# KeyJam_Header.net
KiCad netlist of a schematic drawn in EAGLE
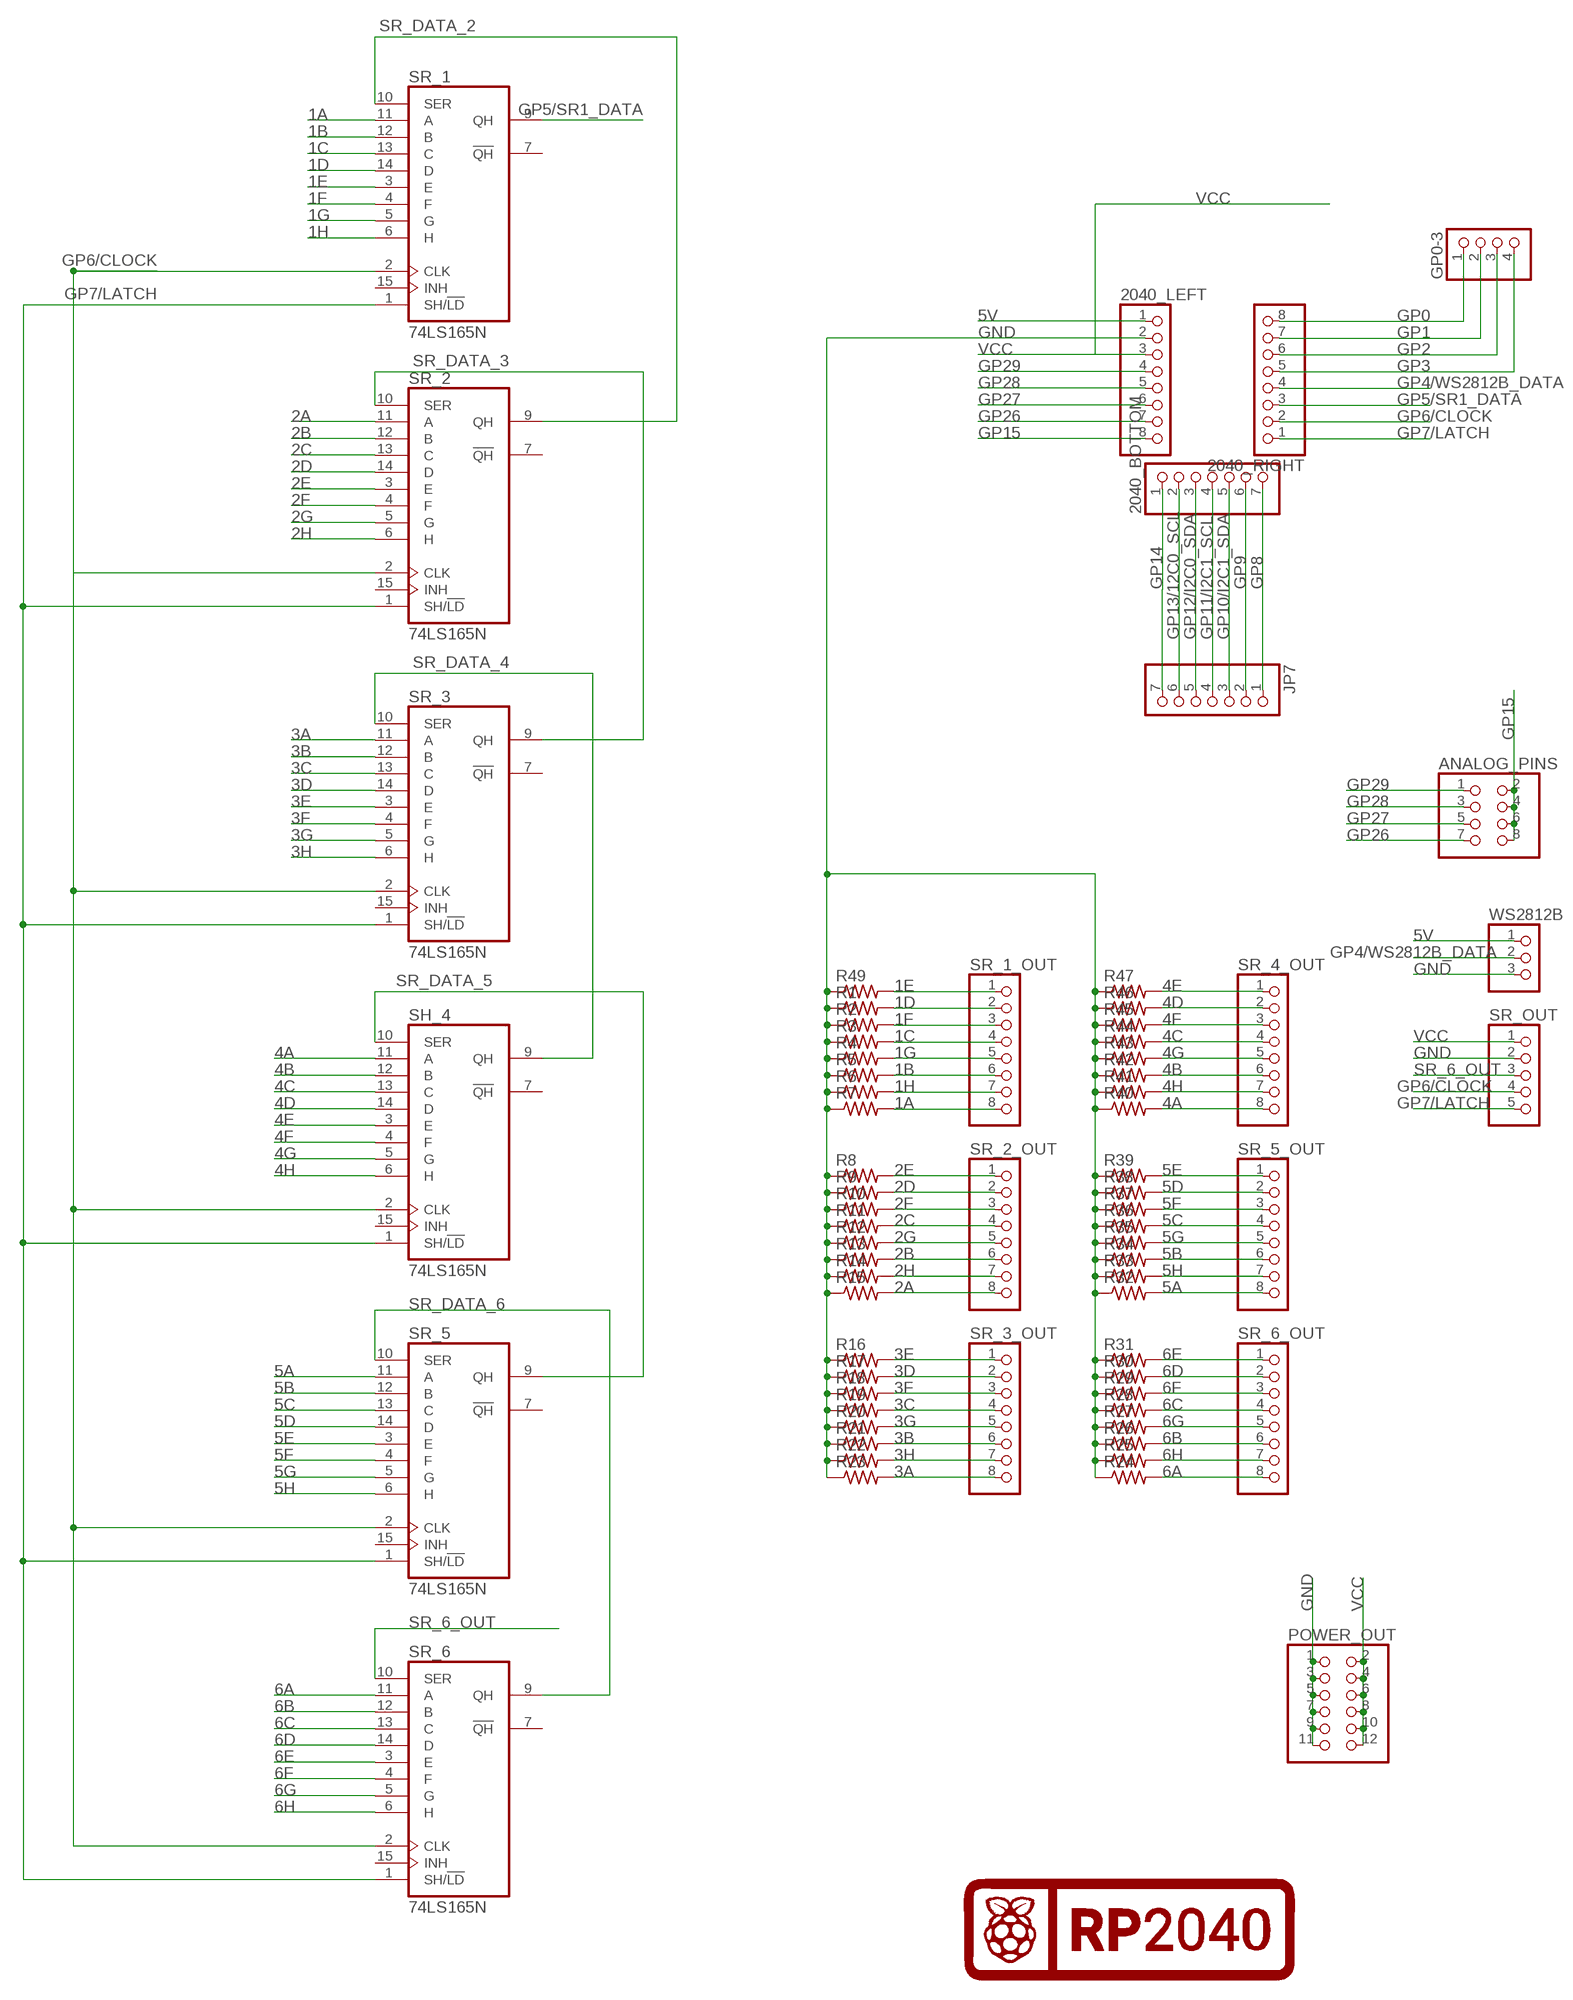
[diagram p0: schematic, sheet 1]

(export (version "E")
  (design (tool "Eeschema 10.0.6"))
  (components
    (comp (ref "2040_BOTTOM")
      (value "PINHD-1X7")
      (footprint "eagle-import:1X07")
      (libsource (lib "eagle-import") (part "PINHD-1X7"))
    )
    (comp (ref "2040_LEFT")
      (value "PINHD-1X8")
      (footprint "eagle-import:1X08")
      (libsource (lib "eagle-import") (part "PINHD-1X8"))
    )
    (comp (ref "2040_RIGHT")
      (value "PINHD-1X8")
      (footprint "eagle-import:1X08")
      (libsource (lib "eagle-import") (part "PINHD-1X8"))
    )
    (comp (ref "ANALOG_PINS")
      (value "PINHD-2X4")
      (footprint "eagle-import:2X04")
      (libsource (lib "eagle-import") (part "PINHD-2X4"))
    )
    (comp (ref "GP0-3")
      (value "PINHD-1X4")
      (footprint "eagle-import:1X04")
      (libsource (lib "eagle-import") (part "PINHD-1X4"))
    )
    (comp (ref "JP7")
      (value "PINHD-1X7")
      (footprint "eagle-import:1X07")
      (libsource (lib "eagle-import") (part "PINHD-1X7"))
    )
    (comp (ref "POWER_OUT")
      (value "PINHD-2X6")
      (footprint "eagle-import:2X06")
      (libsource (lib "eagle-import") (part "PINHD-2X6"))
    )
    (comp (ref "R1")
      (value "R-US_R1206")
      (footprint "eagle-import:R1206")
      (libsource (lib "eagle-import") (part "R-US_R1206"))
    )
    (comp (ref "R2")
      (value "R-US_R1206")
      (footprint "eagle-import:R1206")
      (libsource (lib "eagle-import") (part "R-US_R1206"))
    )
    (comp (ref "R3")
      (value "R-US_R1206")
      (footprint "eagle-import:R1206")
      (libsource (lib "eagle-import") (part "R-US_R1206"))
    )
    (comp (ref "R4")
      (value "R-US_R1206")
      (footprint "eagle-import:R1206")
      (libsource (lib "eagle-import") (part "R-US_R1206"))
    )
    (comp (ref "R5")
      (value "R-US_R1206")
      (footprint "eagle-import:R1206")
      (libsource (lib "eagle-import") (part "R-US_R1206"))
    )
    (comp (ref "R6")
      (value "R-US_R1206")
      (footprint "eagle-import:R1206")
      (libsource (lib "eagle-import") (part "R-US_R1206"))
    )
    (comp (ref "R7")
      (value "R-US_R1206")
      (footprint "eagle-import:R1206")
      (libsource (lib "eagle-import") (part "R-US_R1206"))
    )
    (comp (ref "R8")
      (value "R-US_R1206")
      (footprint "eagle-import:R1206")
      (libsource (lib "eagle-import") (part "R-US_R1206"))
    )
    (comp (ref "R9")
      (value "R-US_R1206")
      (footprint "eagle-import:R1206")
      (libsource (lib "eagle-import") (part "R-US_R1206"))
    )
    (comp (ref "R10")
      (value "R-US_R1206")
      (footprint "eagle-import:R1206")
      (libsource (lib "eagle-import") (part "R-US_R1206"))
    )
    (comp (ref "R11")
      (value "R-US_R1206")
      (footprint "eagle-import:R1206")
      (libsource (lib "eagle-import") (part "R-US_R1206"))
    )
    (comp (ref "R12")
      (value "R-US_R1206")
      (footprint "eagle-import:R1206")
      (libsource (lib "eagle-import") (part "R-US_R1206"))
    )
    (comp (ref "R13")
      (value "R-US_R1206")
      (footprint "eagle-import:R1206")
      (libsource (lib "eagle-import") (part "R-US_R1206"))
    )
    (comp (ref "R14")
      (value "R-US_R1206")
      (footprint "eagle-import:R1206")
      (libsource (lib "eagle-import") (part "R-US_R1206"))
    )
    (comp (ref "R15")
      (value "R-US_R1206")
      (footprint "eagle-import:R1206")
      (libsource (lib "eagle-import") (part "R-US_R1206"))
    )
    (comp (ref "R16")
      (value "R-US_R1206")
      (footprint "eagle-import:R1206")
      (libsource (lib "eagle-import") (part "R-US_R1206"))
    )
    (comp (ref "R17")
      (value "R-US_R1206")
      (footprint "eagle-import:R1206")
      (libsource (lib "eagle-import") (part "R-US_R1206"))
    )
    (comp (ref "R18")
      (value "R-US_R1206")
      (footprint "eagle-import:R1206")
      (libsource (lib "eagle-import") (part "R-US_R1206"))
    )
    (comp (ref "R19")
      (value "R-US_R1206")
      (footprint "eagle-import:R1206")
      (libsource (lib "eagle-import") (part "R-US_R1206"))
    )
    (comp (ref "R20")
      (value "R-US_R1206")
      (footprint "eagle-import:R1206")
      (libsource (lib "eagle-import") (part "R-US_R1206"))
    )
    (comp (ref "R21")
      (value "R-US_R1206")
      (footprint "eagle-import:R1206")
      (libsource (lib "eagle-import") (part "R-US_R1206"))
    )
    (comp (ref "R22")
      (value "R-US_R1206")
      (footprint "eagle-import:R1206")
      (libsource (lib "eagle-import") (part "R-US_R1206"))
    )
    (comp (ref "R23")
      (value "R-US_R1206")
      (footprint "eagle-import:R1206")
      (libsource (lib "eagle-import") (part "R-US_R1206"))
    )
    (comp (ref "R24")
      (value "R-US_R1206")
      (footprint "eagle-import:R1206")
      (libsource (lib "eagle-import") (part "R-US_R1206"))
    )
    (comp (ref "R25")
      (value "R-US_R1206")
      (footprint "eagle-import:R1206")
      (libsource (lib "eagle-import") (part "R-US_R1206"))
    )
    (comp (ref "R26")
      (value "R-US_R1206")
      (footprint "eagle-import:R1206")
      (libsource (lib "eagle-import") (part "R-US_R1206"))
    )
    (comp (ref "R27")
      (value "R-US_R1206")
      (footprint "eagle-import:R1206")
      (libsource (lib "eagle-import") (part "R-US_R1206"))
    )
    (comp (ref "R28")
      (value "R-US_R1206")
      (footprint "eagle-import:R1206")
      (libsource (lib "eagle-import") (part "R-US_R1206"))
    )
    (comp (ref "R29")
      (value "R-US_R1206")
      (footprint "eagle-import:R1206")
      (libsource (lib "eagle-import") (part "R-US_R1206"))
    )
    (comp (ref "R30")
      (value "R-US_R1206")
      (footprint "eagle-import:R1206")
      (libsource (lib "eagle-import") (part "R-US_R1206"))
    )
    (comp (ref "R31")
      (value "R-US_R1206")
      (footprint "eagle-import:R1206")
      (libsource (lib "eagle-import") (part "R-US_R1206"))
    )
    (comp (ref "R32")
      (value "R-US_R1206")
      (footprint "eagle-import:R1206")
      (libsource (lib "eagle-import") (part "R-US_R1206"))
    )
    (comp (ref "R33")
      (value "R-US_R1206")
      (footprint "eagle-import:R1206")
      (libsource (lib "eagle-import") (part "R-US_R1206"))
    )
    (comp (ref "R34")
      (value "R-US_R1206")
      (footprint "eagle-import:R1206")
      (libsource (lib "eagle-import") (part "R-US_R1206"))
    )
    (comp (ref "R35")
      (value "R-US_R1206")
      (footprint "eagle-import:R1206")
      (libsource (lib "eagle-import") (part "R-US_R1206"))
    )
    (comp (ref "R36")
      (value "R-US_R1206")
      (footprint "eagle-import:R1206")
      (libsource (lib "eagle-import") (part "R-US_R1206"))
    )
    (comp (ref "R37")
      (value "R-US_R1206")
      (footprint "eagle-import:R1206")
      (libsource (lib "eagle-import") (part "R-US_R1206"))
    )
    (comp (ref "R38")
      (value "R-US_R1206")
      (footprint "eagle-import:R1206")
      (libsource (lib "eagle-import") (part "R-US_R1206"))
    )
    (comp (ref "R39")
      (value "R-US_R1206")
      (footprint "eagle-import:R1206")
      (libsource (lib "eagle-import") (part "R-US_R1206"))
    )
    (comp (ref "R40")
      (value "R-US_R1206")
      (footprint "eagle-import:R1206")
      (libsource (lib "eagle-import") (part "R-US_R1206"))
    )
    (comp (ref "R41")
      (value "R-US_R1206")
      (footprint "eagle-import:R1206")
      (libsource (lib "eagle-import") (part "R-US_R1206"))
    )
    (comp (ref "R42")
      (value "R-US_R1206")
      (footprint "eagle-import:R1206")
      (libsource (lib "eagle-import") (part "R-US_R1206"))
    )
    (comp (ref "R43")
      (value "R-US_R1206")
      (footprint "eagle-import:R1206")
      (libsource (lib "eagle-import") (part "R-US_R1206"))
    )
    (comp (ref "R44")
      (value "R-US_R1206")
      (footprint "eagle-import:R1206")
      (libsource (lib "eagle-import") (part "R-US_R1206"))
    )
    (comp (ref "R45")
      (value "R-US_R1206")
      (footprint "eagle-import:R1206")
      (libsource (lib "eagle-import") (part "R-US_R1206"))
    )
    (comp (ref "R46")
      (value "R-US_R1206")
      (footprint "eagle-import:R1206")
      (libsource (lib "eagle-import") (part "R-US_R1206"))
    )
    (comp (ref "R47")
      (value "R-US_R1206")
      (footprint "eagle-import:R1206")
      (libsource (lib "eagle-import") (part "R-US_R1206"))
    )
    (comp (ref "R49")
      (value "R-US_R1206")
      (footprint "eagle-import:R1206")
      (libsource (lib "eagle-import") (part "R-US_R1206"))
    )
    (comp (ref "SH_4")
      (value "74LS165N")
      (footprint "eagle-import:DIL16")
      (libsource (lib "eagle-import") (part "74165NLS"))
    )
    (comp (ref "SR_1")
      (value "74LS165N")
      (footprint "eagle-import:DIL16")
      (libsource (lib "eagle-import") (part "74165NLS"))
    )
    (comp (ref "SR_1_OUT")
      (value "PINHD-1X8")
      (footprint "eagle-import:1X08")
      (libsource (lib "eagle-import") (part "PINHD-1X8"))
    )
    (comp (ref "SR_2")
      (value "74LS165N")
      (footprint "eagle-import:DIL16")
      (libsource (lib "eagle-import") (part "74165NLS"))
    )
    (comp (ref "SR_2_OUT")
      (value "PINHD-1X8")
      (footprint "eagle-import:1X08")
      (libsource (lib "eagle-import") (part "PINHD-1X8"))
    )
    (comp (ref "SR_3")
      (value "74LS165N")
      (footprint "eagle-import:DIL16")
      (libsource (lib "eagle-import") (part "74165NLS"))
    )
    (comp (ref "SR_3_OUT")
      (value "PINHD-1X8")
      (footprint "eagle-import:1X08")
      (libsource (lib "eagle-import") (part "PINHD-1X8"))
    )
    (comp (ref "SR_4_OUT")
      (value "PINHD-1X8")
      (footprint "eagle-import:1X08")
      (libsource (lib "eagle-import") (part "PINHD-1X8"))
    )
    (comp (ref "SR_5")
      (value "74LS165N")
      (footprint "eagle-import:DIL16")
      (libsource (lib "eagle-import") (part "74165NLS"))
    )
    (comp (ref "SR_5_OUT")
      (value "PINHD-1X8")
      (footprint "eagle-import:1X08")
      (libsource (lib "eagle-import") (part "PINHD-1X8"))
    )
    (comp (ref "SR_6")
      (value "74LS165N")
      (footprint "eagle-import:DIL16")
      (libsource (lib "eagle-import") (part "74165NLS"))
    )
    (comp (ref "SR_6_OUT")
      (value "PINHD-1X8")
      (footprint "eagle-import:1X08")
      (libsource (lib "eagle-import") (part "PINHD-1X8"))
    )
    (comp (ref "SR_OUT")
      (value "PINHD-1X5")
      (footprint "eagle-import:1X05")
      (libsource (lib "eagle-import") (part "PINHD-1X5"))
    )
    (comp (ref "U$1")
      (value "RASPI_RP2040_LOGO_20MM")
      (footprint "eagle-import:RASPI_RP2040_LOGO_20MM")
      (libsource (lib "eagle-import") (part "RASPI_RP2040_LOGO_20MM"))
    )
    (comp (ref "WS2812B")
      (value "PINHD-1X3")
      (footprint "eagle-import:1X03")
      (libsource (lib "eagle-import") (part "PINHD-1X3"))
    )
  )
  (nets
    (net (code "1") (name "/1A") (class "Default")
      (node (ref "R7") (pin "2") (pinfunction "2_2") (pintype "passive"))
      (node (ref "SR_1") (pin "11") (pinfunction "A_11") (pintype "input"))
      (node (ref "SR_1_OUT") (pin "8") (pinfunction "8_8") (pintype "passive"))
    )
    (net (code "2") (name "/1B") (class "Default")
      (node (ref "R5") (pin "2") (pinfunction "2_2") (pintype "passive"))
      (node (ref "SR_1") (pin "12") (pinfunction "B_12") (pintype "input"))
      (node (ref "SR_1_OUT") (pin "6") (pinfunction "6_6") (pintype "passive"))
    )
    (net (code "3") (name "/1C") (class "Default")
      (node (ref "R3") (pin "2") (pinfunction "2_2") (pintype "passive"))
      (node (ref "SR_1") (pin "13") (pinfunction "C_13") (pintype "input"))
      (node (ref "SR_1_OUT") (pin "4") (pinfunction "4_4") (pintype "passive"))
    )
    (net (code "4") (name "/1D") (class "Default")
      (node (ref "R1") (pin "2") (pinfunction "2_2") (pintype "passive"))
      (node (ref "SR_1") (pin "14") (pinfunction "D_14") (pintype "input"))
      (node (ref "SR_1_OUT") (pin "2") (pinfunction "2_2") (pintype "passive"))
    )
    (net (code "5") (name "/1E") (class "Default")
      (node (ref "R49") (pin "2") (pinfunction "2_2") (pintype "passive"))
      (node (ref "SR_1") (pin "3") (pinfunction "E_3") (pintype "input"))
      (node (ref "SR_1_OUT") (pin "1") (pinfunction "1_1") (pintype "passive"))
    )
    (net (code "6") (name "/1F") (class "Default")
      (node (ref "R2") (pin "2") (pinfunction "2_2") (pintype "passive"))
      (node (ref "SR_1") (pin "4") (pinfunction "F_4") (pintype "input"))
      (node (ref "SR_1_OUT") (pin "3") (pinfunction "3_3") (pintype "passive"))
    )
    (net (code "7") (name "/1G") (class "Default")
      (node (ref "R4") (pin "2") (pinfunction "2_2") (pintype "passive"))
      (node (ref "SR_1") (pin "5") (pinfunction "G_5") (pintype "input"))
      (node (ref "SR_1_OUT") (pin "5") (pinfunction "5_5") (pintype "passive"))
    )
    (net (code "8") (name "/1H") (class "Default")
      (node (ref "R6") (pin "2") (pinfunction "2_2") (pintype "passive"))
      (node (ref "SR_1") (pin "6") (pinfunction "H_6") (pintype "input"))
      (node (ref "SR_1_OUT") (pin "7") (pinfunction "7_7") (pintype "passive"))
    )
    (net (code "9") (name "/2A") (class "Default")
      (node (ref "R15") (pin "2") (pinfunction "2_2") (pintype "passive"))
      (node (ref "SR_2") (pin "11") (pinfunction "A_11") (pintype "input"))
      (node (ref "SR_2_OUT") (pin "8") (pinfunction "8_8") (pintype "passive"))
    )
    (net (code "10") (name "/2B") (class "Default")
      (node (ref "R13") (pin "2") (pinfunction "2_2") (pintype "passive"))
      (node (ref "SR_2") (pin "12") (pinfunction "B_12") (pintype "input"))
      (node (ref "SR_2_OUT") (pin "6") (pinfunction "6_6") (pintype "passive"))
    )
    (net (code "11") (name "/2C") (class "Default")
      (node (ref "R11") (pin "2") (pinfunction "2_2") (pintype "passive"))
      (node (ref "SR_2") (pin "13") (pinfunction "C_13") (pintype "input"))
      (node (ref "SR_2_OUT") (pin "4") (pinfunction "4_4") (pintype "passive"))
    )
    (net (code "12") (name "/2D") (class "Default")
      (node (ref "R9") (pin "2") (pinfunction "2_2") (pintype "passive"))
      (node (ref "SR_2") (pin "14") (pinfunction "D_14") (pintype "input"))
      (node (ref "SR_2_OUT") (pin "2") (pinfunction "2_2") (pintype "passive"))
    )
    (net (code "13") (name "/2E") (class "Default")
      (node (ref "R8") (pin "2") (pinfunction "2_2") (pintype "passive"))
      (node (ref "SR_2") (pin "3") (pinfunction "E_3") (pintype "input"))
      (node (ref "SR_2_OUT") (pin "1") (pinfunction "1_1") (pintype "passive"))
    )
    (net (code "14") (name "/2F") (class "Default")
      (node (ref "R10") (pin "2") (pinfunction "2_2") (pintype "passive"))
      (node (ref "SR_2") (pin "4") (pinfunction "F_4") (pintype "input"))
      (node (ref "SR_2_OUT") (pin "3") (pinfunction "3_3") (pintype "passive"))
    )
    (net (code "15") (name "/2G") (class "Default")
      (node (ref "R12") (pin "2") (pinfunction "2_2") (pintype "passive"))
      (node (ref "SR_2") (pin "5") (pinfunction "G_5") (pintype "input"))
      (node (ref "SR_2_OUT") (pin "5") (pinfunction "5_5") (pintype "passive"))
    )
    (net (code "16") (name "/2H") (class "Default")
      (node (ref "R14") (pin "2") (pinfunction "2_2") (pintype "passive"))
      (node (ref "SR_2") (pin "6") (pinfunction "H_6") (pintype "input"))
      (node (ref "SR_2_OUT") (pin "7") (pinfunction "7_7") (pintype "passive"))
    )
    (net (code "17") (name "/3A") (class "Default")
      (node (ref "R23") (pin "2") (pinfunction "2_2") (pintype "passive"))
      (node (ref "SR_3") (pin "11") (pinfunction "A_11") (pintype "input"))
      (node (ref "SR_3_OUT") (pin "8") (pinfunction "8_8") (pintype "passive"))
    )
    (net (code "18") (name "/3B") (class "Default")
      (node (ref "R21") (pin "2") (pinfunction "2_2") (pintype "passive"))
      (node (ref "SR_3") (pin "12") (pinfunction "B_12") (pintype "input"))
      (node (ref "SR_3_OUT") (pin "6") (pinfunction "6_6") (pintype "passive"))
    )
    (net (code "19") (name "/3C") (class "Default")
      (node (ref "R19") (pin "2") (pinfunction "2_2") (pintype "passive"))
      (node (ref "SR_3") (pin "13") (pinfunction "C_13") (pintype "input"))
      (node (ref "SR_3_OUT") (pin "4") (pinfunction "4_4") (pintype "passive"))
    )
    (net (code "20") (name "/3D") (class "Default")
      (node (ref "R17") (pin "2") (pinfunction "2_2") (pintype "passive"))
      (node (ref "SR_3") (pin "14") (pinfunction "D_14") (pintype "input"))
      (node (ref "SR_3_OUT") (pin "2") (pinfunction "2_2") (pintype "passive"))
    )
    (net (code "21") (name "/3E") (class "Default")
      (node (ref "R16") (pin "2") (pinfunction "2_2") (pintype "passive"))
      (node (ref "SR_3") (pin "3") (pinfunction "E_3") (pintype "input"))
      (node (ref "SR_3_OUT") (pin "1") (pinfunction "1_1") (pintype "passive"))
    )
    (net (code "22") (name "/3F") (class "Default")
      (node (ref "R18") (pin "2") (pinfunction "2_2") (pintype "passive"))
      (node (ref "SR_3") (pin "4") (pinfunction "F_4") (pintype "input"))
      (node (ref "SR_3_OUT") (pin "3") (pinfunction "3_3") (pintype "passive"))
    )
    (net (code "23") (name "/3G") (class "Default")
      (node (ref "R20") (pin "2") (pinfunction "2_2") (pintype "passive"))
      (node (ref "SR_3") (pin "5") (pinfunction "G_5") (pintype "input"))
      (node (ref "SR_3_OUT") (pin "5") (pinfunction "5_5") (pintype "passive"))
    )
    (net (code "24") (name "/3H") (class "Default")
      (node (ref "R22") (pin "2") (pinfunction "2_2") (pintype "passive"))
      (node (ref "SR_3") (pin "6") (pinfunction "H_6") (pintype "input"))
      (node (ref "SR_3_OUT") (pin "7") (pinfunction "7_7") (pintype "passive"))
    )
    (net (code "25") (name "/4A") (class "Default")
      (node (ref "R40") (pin "2") (pinfunction "2_2") (pintype "passive"))
      (node (ref "SH_4") (pin "11") (pinfunction "A_11") (pintype "input"))
      (node (ref "SR_4_OUT") (pin "8") (pinfunction "8_8") (pintype "passive"))
    )
    (net (code "26") (name "/4B") (class "Default")
      (node (ref "R42") (pin "2") (pinfunction "2_2") (pintype "passive"))
      (node (ref "SH_4") (pin "12") (pinfunction "B_12") (pintype "input"))
      (node (ref "SR_4_OUT") (pin "6") (pinfunction "6_6") (pintype "passive"))
    )
    (net (code "27") (name "/4C") (class "Default")
      (node (ref "R44") (pin "2") (pinfunction "2_2") (pintype "passive"))
      (node (ref "SH_4") (pin "13") (pinfunction "C_13") (pintype "input"))
      (node (ref "SR_4_OUT") (pin "4") (pinfunction "4_4") (pintype "passive"))
    )
    (net (code "28") (name "/4D") (class "Default")
      (node (ref "R46") (pin "2") (pinfunction "2_2") (pintype "passive"))
      (node (ref "SH_4") (pin "14") (pinfunction "D_14") (pintype "input"))
      (node (ref "SR_4_OUT") (pin "2") (pinfunction "2_2") (pintype "passive"))
    )
    (net (code "29") (name "/4E") (class "Default")
      (node (ref "R47") (pin "2") (pinfunction "2_2") (pintype "passive"))
      (node (ref "SH_4") (pin "3") (pinfunction "E_3") (pintype "input"))
      (node (ref "SR_4_OUT") (pin "1") (pinfunction "1_1") (pintype "passive"))
    )
    (net (code "30") (name "/4F") (class "Default")
      (node (ref "R45") (pin "2") (pinfunction "2_2") (pintype "passive"))
      (node (ref "SH_4") (pin "4") (pinfunction "F_4") (pintype "input"))
      (node (ref "SR_4_OUT") (pin "3") (pinfunction "3_3") (pintype "passive"))
    )
    (net (code "31") (name "/4G") (class "Default")
      (node (ref "R43") (pin "2") (pinfunction "2_2") (pintype "passive"))
      (node (ref "SH_4") (pin "5") (pinfunction "G_5") (pintype "input"))
      (node (ref "SR_4_OUT") (pin "5") (pinfunction "5_5") (pintype "passive"))
    )
    (net (code "32") (name "/4H") (class "Default")
      (node (ref "R41") (pin "2") (pinfunction "2_2") (pintype "passive"))
      (node (ref "SH_4") (pin "6") (pinfunction "H_6") (pintype "input"))
      (node (ref "SR_4_OUT") (pin "7") (pinfunction "7_7") (pintype "passive"))
    )
    (net (code "33") (name "/5A") (class "Default")
      (node (ref "R32") (pin "2") (pinfunction "2_2") (pintype "passive"))
      (node (ref "SR_5") (pin "11") (pinfunction "A_11") (pintype "input"))
      (node (ref "SR_5_OUT") (pin "8") (pinfunction "8_8") (pintype "passive"))
    )
    (net (code "34") (name "/5B") (class "Default")
      (node (ref "R34") (pin "2") (pinfunction "2_2") (pintype "passive"))
      (node (ref "SR_5") (pin "12") (pinfunction "B_12") (pintype "input"))
      (node (ref "SR_5_OUT") (pin "6") (pinfunction "6_6") (pintype "passive"))
    )
    (net (code "35") (name "/5C") (class "Default")
      (node (ref "R36") (pin "2") (pinfunction "2_2") (pintype "passive"))
      (node (ref "SR_5") (pin "13") (pinfunction "C_13") (pintype "input"))
      (node (ref "SR_5_OUT") (pin "4") (pinfunction "4_4") (pintype "passive"))
    )
    (net (code "36") (name "/5D") (class "Default")
      (node (ref "R38") (pin "2") (pinfunction "2_2") (pintype "passive"))
      (node (ref "SR_5") (pin "14") (pinfunction "D_14") (pintype "input"))
      (node (ref "SR_5_OUT") (pin "2") (pinfunction "2_2") (pintype "passive"))
    )
    (net (code "37") (name "/5E") (class "Default")
      (node (ref "R39") (pin "2") (pinfunction "2_2") (pintype "passive"))
      (node (ref "SR_5") (pin "3") (pinfunction "E_3") (pintype "input"))
      (node (ref "SR_5_OUT") (pin "1") (pinfunction "1_1") (pintype "passive"))
    )
    (net (code "38") (name "/5F") (class "Default")
      (node (ref "R37") (pin "2") (pinfunction "2_2") (pintype "passive"))
      (node (ref "SR_5") (pin "4") (pinfunction "F_4") (pintype "input"))
      (node (ref "SR_5_OUT") (pin "3") (pinfunction "3_3") (pintype "passive"))
    )
    (net (code "39") (name "/5G") (class "Default")
      (node (ref "R35") (pin "2") (pinfunction "2_2") (pintype "passive"))
      (node (ref "SR_5") (pin "5") (pinfunction "G_5") (pintype "input"))
      (node (ref "SR_5_OUT") (pin "5") (pinfunction "5_5") (pintype "passive"))
    )
    (net (code "40") (name "/5H") (class "Default")
      (node (ref "R33") (pin "2") (pinfunction "2_2") (pintype "passive"))
      (node (ref "SR_5") (pin "6") (pinfunction "H_6") (pintype "input"))
      (node (ref "SR_5_OUT") (pin "7") (pinfunction "7_7") (pintype "passive"))
    )
    (net (code "41") (name "/5V") (class "Default")
      (node (ref "2040_LEFT") (pin "1") (pinfunction "1_1") (pintype "passive"))
      (node (ref "WS2812B") (pin "1") (pinfunction "1_1") (pintype "passive"))
    )
    (net (code "42") (name "/6A") (class "Default")
      (node (ref "R24") (pin "2") (pinfunction "2_2") (pintype "passive"))
      (node (ref "SR_6") (pin "11") (pinfunction "A_11") (pintype "input"))
      (node (ref "SR_6_OUT") (pin "8") (pinfunction "8_8") (pintype "passive"))
    )
    (net (code "43") (name "/6B") (class "Default")
      (node (ref "R26") (pin "2") (pinfunction "2_2") (pintype "passive"))
      (node (ref "SR_6") (pin "12") (pinfunction "B_12") (pintype "input"))
      (node (ref "SR_6_OUT") (pin "6") (pinfunction "6_6") (pintype "passive"))
    )
    (net (code "44") (name "/6C") (class "Default")
      (node (ref "R28") (pin "2") (pinfunction "2_2") (pintype "passive"))
      (node (ref "SR_6") (pin "13") (pinfunction "C_13") (pintype "input"))
      (node (ref "SR_6_OUT") (pin "4") (pinfunction "4_4") (pintype "passive"))
    )
    (net (code "45") (name "/6D") (class "Default")
      (node (ref "R30") (pin "2") (pinfunction "2_2") (pintype "passive"))
      (node (ref "SR_6") (pin "14") (pinfunction "D_14") (pintype "input"))
      (node (ref "SR_6_OUT") (pin "2") (pinfunction "2_2") (pintype "passive"))
    )
    (net (code "46") (name "/6E") (class "Default")
      (node (ref "R31") (pin "2") (pinfunction "2_2") (pintype "passive"))
      (node (ref "SR_6") (pin "3") (pinfunction "E_3") (pintype "input"))
      (node (ref "SR_6_OUT") (pin "1") (pinfunction "1_1") (pintype "passive"))
    )
    (net (code "47") (name "/6F") (class "Default")
      (node (ref "R29") (pin "2") (pinfunction "2_2") (pintype "passive"))
      (node (ref "SR_6") (pin "4") (pinfunction "F_4") (pintype "input"))
      (node (ref "SR_6_OUT") (pin "3") (pinfunction "3_3") (pintype "passive"))
    )
    (net (code "48") (name "/6G") (class "Default")
      (node (ref "R27") (pin "2") (pinfunction "2_2") (pintype "passive"))
      (node (ref "SR_6") (pin "5") (pinfunction "G_5") (pintype "input"))
      (node (ref "SR_6_OUT") (pin "5") (pinfunction "5_5") (pintype "passive"))
    )
    (net (code "49") (name "/6H") (class "Default")
      (node (ref "R25") (pin "2") (pinfunction "2_2") (pintype "passive"))
      (node (ref "SR_6") (pin "6") (pinfunction "H_6") (pintype "input"))
      (node (ref "SR_6_OUT") (pin "7") (pinfunction "7_7") (pintype "passive"))
    )
    (net (code "50") (name "/GND") (class "Default")
      (node (ref "2040_LEFT") (pin "2") (pinfunction "2_2") (pintype "passive"))
      (node (ref "POWER_OUT") (pin "1") (pinfunction "1_1") (pintype "passive"))
      (node (ref "POWER_OUT") (pin "11") (pinfunction "11_11") (pintype "passive"))
      (node (ref "POWER_OUT") (pin "3") (pinfunction "3_3") (pintype "passive"))
      (node (ref "POWER_OUT") (pin "5") (pinfunction "5_5") (pintype "passive"))
      (node (ref "POWER_OUT") (pin "7") (pinfunction "7_7") (pintype "passive"))
      (node (ref "POWER_OUT") (pin "9") (pinfunction "9_9") (pintype "passive"))
      (node (ref "R1") (pin "1") (pinfunction "1_1") (pintype "passive"))
      (node (ref "R10") (pin "1") (pinfunction "1_1") (pintype "passive"))
      (node (ref "R11") (pin "1") (pinfunction "1_1") (pintype "passive"))
      (node (ref "R12") (pin "1") (pinfunction "1_1") (pintype "passive"))
      (node (ref "R13") (pin "1") (pinfunction "1_1") (pintype "passive"))
      (node (ref "R14") (pin "1") (pinfunction "1_1") (pintype "passive"))
      (node (ref "R15") (pin "1") (pinfunction "1_1") (pintype "passive"))
      (node (ref "R16") (pin "1") (pinfunction "1_1") (pintype "passive"))
      (node (ref "R17") (pin "1") (pinfunction "1_1") (pintype "passive"))
      (node (ref "R18") (pin "1") (pinfunction "1_1") (pintype "passive"))
      (node (ref "R19") (pin "1") (pinfunction "1_1") (pintype "passive"))
      (node (ref "R2") (pin "1") (pinfunction "1_1") (pintype "passive"))
      (node (ref "R20") (pin "1") (pinfunction "1_1") (pintype "passive"))
      (node (ref "R21") (pin "1") (pinfunction "1_1") (pintype "passive"))
      (node (ref "R22") (pin "1") (pinfunction "1_1") (pintype "passive"))
      (node (ref "R23") (pin "1") (pinfunction "1_1") (pintype "passive"))
      (node (ref "R24") (pin "1") (pinfunction "1_1") (pintype "passive"))
      (node (ref "R25") (pin "1") (pinfunction "1_1") (pintype "passive"))
      (node (ref "R26") (pin "1") (pinfunction "1_1") (pintype "passive"))
      (node (ref "R27") (pin "1") (pinfunction "1_1") (pintype "passive"))
      (node (ref "R28") (pin "1") (pinfunction "1_1") (pintype "passive"))
      (node (ref "R29") (pin "1") (pinfunction "1_1") (pintype "passive"))
      (node (ref "R3") (pin "1") (pinfunction "1_1") (pintype "passive"))
      (node (ref "R30") (pin "1") (pinfunction "1_1") (pintype "passive"))
      (node (ref "R31") (pin "1") (pinfunction "1_1") (pintype "passive"))
      (node (ref "R32") (pin "1") (pinfunction "1_1") (pintype "passive"))
      (node (ref "R33") (pin "1") (pinfunction "1_1") (pintype "passive"))
      (node (ref "R34") (pin "1") (pinfunction "1_1") (pintype "passive"))
      (node (ref "R35") (pin "1") (pinfunction "1_1") (pintype "passive"))
      (node (ref "R36") (pin "1") (pinfunction "1_1") (pintype "passive"))
      (node (ref "R37") (pin "1") (pinfunction "1_1") (pintype "passive"))
      (node (ref "R38") (pin "1") (pinfunction "1_1") (pintype "passive"))
      (node (ref "R39") (pin "1") (pinfunction "1_1") (pintype "passive"))
      (node (ref "R4") (pin "1") (pinfunction "1_1") (pintype "passive"))
      (node (ref "R40") (pin "1") (pinfunction "1_1") (pintype "passive"))
      (node (ref "R41") (pin "1") (pinfunction "1_1") (pintype "passive"))
      (node (ref "R42") (pin "1") (pinfunction "1_1") (pintype "passive"))
      (node (ref "R43") (pin "1") (pinfunction "1_1") (pintype "passive"))
      (node (ref "R44") (pin "1") (pinfunction "1_1") (pintype "passive"))
      (node (ref "R45") (pin "1") (pinfunction "1_1") (pintype "passive"))
      (node (ref "R46") (pin "1") (pinfunction "1_1") (pintype "passive"))
      (node (ref "R47") (pin "1") (pinfunction "1_1") (pintype "passive"))
      (node (ref "R49") (pin "1") (pinfunction "1_1") (pintype "passive"))
      (node (ref "R5") (pin "1") (pinfunction "1_1") (pintype "passive"))
      (node (ref "R6") (pin "1") (pinfunction "1_1") (pintype "passive"))
      (node (ref "R7") (pin "1") (pinfunction "1_1") (pintype "passive"))
      (node (ref "R8") (pin "1") (pinfunction "1_1") (pintype "passive"))
      (node (ref "R9") (pin "1") (pinfunction "1_1") (pintype "passive"))
      (node (ref "SR_OUT") (pin "2") (pinfunction "2_2") (pintype "passive"))
      (node (ref "WS2812B") (pin "3") (pinfunction "3_3") (pintype "passive"))
    )
    (net (code "51") (name "/GP0") (class "Default")
      (node (ref "2040_RIGHT") (pin "8") (pinfunction "8_8") (pintype "passive"))
      (node (ref "GP0-3") (pin "1") (pinfunction "1_1") (pintype "passive"))
    )
    (net (code "52") (name "/GP1") (class "Default")
      (node (ref "2040_RIGHT") (pin "7") (pinfunction "7_7") (pintype "passive"))
      (node (ref "GP0-3") (pin "2") (pinfunction "2_2") (pintype "passive"))
    )
    (net (code "53") (name "/GP2") (class "Default")
      (node (ref "2040_RIGHT") (pin "6") (pinfunction "6_6") (pintype "passive"))
      (node (ref "GP0-3") (pin "3") (pinfunction "3_3") (pintype "passive"))
    )
    (net (code "54") (name "/GP3") (class "Default")
      (node (ref "2040_RIGHT") (pin "5") (pinfunction "5_5") (pintype "passive"))
      (node (ref "GP0-3") (pin "4") (pinfunction "4_4") (pintype "passive"))
    )
    (net (code "55") (name "/GP4{slash}WS2812B_DATA") (class "Default")
      (node (ref "2040_RIGHT") (pin "4") (pinfunction "4_4") (pintype "passive"))
      (node (ref "WS2812B") (pin "2") (pinfunction "2_2") (pintype "passive"))
    )
    (net (code "56") (name "/GP5{slash}SR1_DATA") (class "Default")
      (node (ref "2040_RIGHT") (pin "3") (pinfunction "3_3") (pintype "passive"))
      (node (ref "SR_1") (pin "9") (pinfunction "QH_9") (pintype "output"))
    )
    (net (code "57") (name "/GP6{slash}CLOCK") (class "Default")
      (node (ref "2040_RIGHT") (pin "2") (pinfunction "2_2") (pintype "passive"))
      (node (ref "SH_4") (pin "2") (pinfunction "CLK_2") (pintype "input"))
      (node (ref "SR_1") (pin "2") (pinfunction "CLK_2") (pintype "input"))
      (node (ref "SR_2") (pin "2") (pinfunction "CLK_2") (pintype "input"))
      (node (ref "SR_3") (pin "2") (pinfunction "CLK_2") (pintype "input"))
      (node (ref "SR_5") (pin "2") (pinfunction "CLK_2") (pintype "input"))
      (node (ref "SR_6") (pin "2") (pinfunction "CLK_2") (pintype "input"))
      (node (ref "SR_OUT") (pin "4") (pinfunction "4_4") (pintype "passive"))
    )
    (net (code "58") (name "/GP7{slash}LATCH") (class "Default")
      (node (ref "2040_RIGHT") (pin "1") (pinfunction "1_1") (pintype "passive"))
      (node (ref "SH_4") (pin "1") (pinfunction "SH/~{LD}_1") (pintype "input"))
      (node (ref "SR_1") (pin "1") (pinfunction "SH/~{LD}_1") (pintype "input"))
      (node (ref "SR_2") (pin "1") (pinfunction "SH/~{LD}_1") (pintype "input"))
      (node (ref "SR_3") (pin "1") (pinfunction "SH/~{LD}_1") (pintype "input"))
      (node (ref "SR_5") (pin "1") (pinfunction "SH/~{LD}_1") (pintype "input"))
      (node (ref "SR_6") (pin "1") (pinfunction "SH/~{LD}_1") (pintype "input"))
      (node (ref "SR_OUT") (pin "5") (pinfunction "5_5") (pintype "passive"))
    )
    (net (code "59") (name "/GP8") (class "Default")
      (node (ref "2040_BOTTOM") (pin "7") (pinfunction "7_7") (pintype "passive"))
      (node (ref "JP7") (pin "1") (pinfunction "1_1") (pintype "passive"))
    )
    (net (code "60") (name "/GP9") (class "Default")
      (node (ref "2040_BOTTOM") (pin "6") (pinfunction "6_6") (pintype "passive"))
      (node (ref "JP7") (pin "2") (pinfunction "2_2") (pintype "passive"))
    )
    (net (code "61") (name "/GP10{slash}I2C1_SDA") (class "Default")
      (node (ref "2040_BOTTOM") (pin "5") (pinfunction "5_5") (pintype "passive"))
      (node (ref "JP7") (pin "3") (pinfunction "3_3") (pintype "passive"))
    )
    (net (code "62") (name "/GP11{slash}I2C1_SCL") (class "Default")
      (node (ref "2040_BOTTOM") (pin "4") (pinfunction "4_4") (pintype "passive"))
      (node (ref "JP7") (pin "4") (pinfunction "4_4") (pintype "passive"))
    )
    (net (code "63") (name "/GP12{slash}I2C0_SDA") (class "Default")
      (node (ref "2040_BOTTOM") (pin "3") (pinfunction "3_3") (pintype "passive"))
      (node (ref "JP7") (pin "5") (pinfunction "5_5") (pintype "passive"))
    )
    (net (code "64") (name "/GP13{slash}12C0_SCL") (class "Default")
      (node (ref "2040_BOTTOM") (pin "2") (pinfunction "2_2") (pintype "passive"))
      (node (ref "JP7") (pin "6") (pinfunction "6_6") (pintype "passive"))
    )
    (net (code "65") (name "/GP14") (class "Default")
      (node (ref "2040_BOTTOM") (pin "1") (pinfunction "1_1") (pintype "passive"))
      (node (ref "JP7") (pin "7") (pinfunction "7_7") (pintype "passive"))
    )
    (net (code "66") (name "/GP15") (class "Default")
      (node (ref "2040_LEFT") (pin "8") (pinfunction "8_8") (pintype "passive"))
      (node (ref "ANALOG_PINS") (pin "2") (pinfunction "2_2") (pintype "passive"))
      (node (ref "ANALOG_PINS") (pin "4") (pinfunction "4_4") (pintype "passive"))
      (node (ref "ANALOG_PINS") (pin "6") (pinfunction "6_6") (pintype "passive"))
      (node (ref "ANALOG_PINS") (pin "8") (pinfunction "8_8") (pintype "passive"))
    )
    (net (code "67") (name "/GP26") (class "Default")
      (node (ref "2040_LEFT") (pin "7") (pinfunction "7_7") (pintype "passive"))
      (node (ref "ANALOG_PINS") (pin "7") (pinfunction "7_7") (pintype "passive"))
    )
    (net (code "68") (name "/GP27") (class "Default")
      (node (ref "2040_LEFT") (pin "6") (pinfunction "6_6") (pintype "passive"))
      (node (ref "ANALOG_PINS") (pin "5") (pinfunction "5_5") (pintype "passive"))
    )
    (net (code "69") (name "/GP28") (class "Default")
      (node (ref "2040_LEFT") (pin "5") (pinfunction "5_5") (pintype "passive"))
      (node (ref "ANALOG_PINS") (pin "3") (pinfunction "3_3") (pintype "passive"))
    )
    (net (code "70") (name "/GP29") (class "Default")
      (node (ref "2040_LEFT") (pin "4") (pinfunction "4_4") (pintype "passive"))
      (node (ref "ANALOG_PINS") (pin "1") (pinfunction "1_1") (pintype "passive"))
    )
    (net (code "71") (name "/SR_6_OUT") (class "Default")
      (node (ref "SR_6") (pin "10") (pinfunction "SER_10") (pintype "input"))
      (node (ref "SR_OUT") (pin "3") (pinfunction "3_3") (pintype "passive"))
    )
    (net (code "72") (name "/SR_DATA_2") (class "Default")
      (node (ref "SR_1") (pin "10") (pinfunction "SER_10") (pintype "input"))
      (node (ref "SR_2") (pin "9") (pinfunction "QH_9") (pintype "output"))
    )
    (net (code "73") (name "/SR_DATA_3") (class "Default")
      (node (ref "SR_2") (pin "10") (pinfunction "SER_10") (pintype "input"))
      (node (ref "SR_3") (pin "9") (pinfunction "QH_9") (pintype "output"))
    )
    (net (code "74") (name "/SR_DATA_4") (class "Default")
      (node (ref "SH_4") (pin "9") (pinfunction "QH_9") (pintype "output"))
      (node (ref "SR_3") (pin "10") (pinfunction "SER_10") (pintype "input"))
    )
    (net (code "75") (name "/SR_DATA_5") (class "Default")
      (node (ref "SH_4") (pin "10") (pinfunction "SER_10") (pintype "input"))
      (node (ref "SR_5") (pin "9") (pinfunction "QH_9") (pintype "output"))
    )
    (net (code "76") (name "/SR_DATA_6") (class "Default")
      (node (ref "SR_5") (pin "10") (pinfunction "SER_10") (pintype "input"))
      (node (ref "SR_6") (pin "9") (pinfunction "QH_9") (pintype "output"))
    )
    (net (code "77") (name "/VCC") (class "Default")
      (node (ref "2040_LEFT") (pin "3") (pinfunction "3_3") (pintype "passive"))
      (node (ref "POWER_OUT") (pin "10") (pinfunction "10_10") (pintype "passive"))
      (node (ref "POWER_OUT") (pin "12") (pinfunction "12_12") (pintype "passive"))
      (node (ref "POWER_OUT") (pin "2") (pinfunction "2_2") (pintype "passive"))
      (node (ref "POWER_OUT") (pin "4") (pinfunction "4_4") (pintype "passive"))
      (node (ref "POWER_OUT") (pin "6") (pinfunction "6_6") (pintype "passive"))
      (node (ref "POWER_OUT") (pin "8") (pinfunction "8_8") (pintype "passive"))
      (node (ref "SR_OUT") (pin "1") (pinfunction "1_1") (pintype "passive"))
    )
    (net (code "78") (name "unconnected-(SH_4A-INH-Pad15)") (class "Default")
      (node (ref "SH_4") (pin "15") (pinfunction "INH_15") (pintype "input"))
    )
    (net (code "79") (name "unconnected-(SH_4A-~{QH}-Pad7)") (class "Default")
      (node (ref "SH_4") (pin "7") (pinfunction "~{QH}_7") (pintype "output"))
    )
    (net (code "80") (name "unconnected-(SR_1A-INH-Pad15)") (class "Default")
      (node (ref "SR_1") (pin "15") (pinfunction "INH_15") (pintype "input"))
    )
    (net (code "81") (name "unconnected-(SR_1A-~{QH}-Pad7)") (class "Default")
      (node (ref "SR_1") (pin "7") (pinfunction "~{QH}_7") (pintype "output"))
    )
    (net (code "82") (name "unconnected-(SR_2A-INH-Pad15)") (class "Default")
      (node (ref "SR_2") (pin "15") (pinfunction "INH_15") (pintype "input"))
    )
    (net (code "83") (name "unconnected-(SR_2A-~{QH}-Pad7)") (class "Default")
      (node (ref "SR_2") (pin "7") (pinfunction "~{QH}_7") (pintype "output"))
    )
    (net (code "84") (name "unconnected-(SR_3A-INH-Pad15)") (class "Default")
      (node (ref "SR_3") (pin "15") (pinfunction "INH_15") (pintype "input"))
    )
    (net (code "85") (name "unconnected-(SR_3A-~{QH}-Pad7)") (class "Default")
      (node (ref "SR_3") (pin "7") (pinfunction "~{QH}_7") (pintype "output"))
    )
    (net (code "86") (name "unconnected-(SR_5A-INH-Pad15)") (class "Default")
      (node (ref "SR_5") (pin "15") (pinfunction "INH_15") (pintype "input"))
    )
    (net (code "87") (name "unconnected-(SR_5A-~{QH}-Pad7)") (class "Default")
      (node (ref "SR_5") (pin "7") (pinfunction "~{QH}_7") (pintype "output"))
    )
    (net (code "88") (name "unconnected-(SR_6A-INH-Pad15)") (class "Default")
      (node (ref "SR_6") (pin "15") (pinfunction "INH_15") (pintype "input"))
    )
    (net (code "89") (name "unconnected-(SR_6A-~{QH}-Pad7)") (class "Default")
      (node (ref "SR_6") (pin "7") (pinfunction "~{QH}_7") (pintype "output"))
    )
  )
)
